# 1_P1.net
KiCad netlist of a schematic drawn in Altium Designer
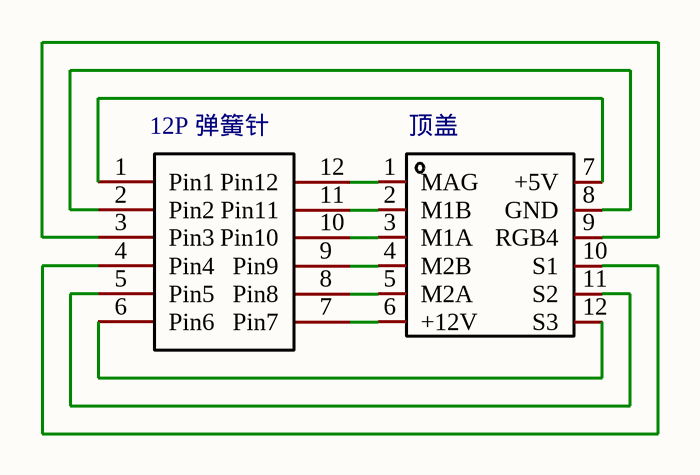
[diagram p0: 1_P1.schdoc]

(export (version "E")
  (design (tool "Eeschema 10.0.6"))
  (components
    (comp (ref "CN1")
      (value "顶盖")
      (description "系列:PHD;连接器类型:接头;触头类型:公形引脚;间距:0.079")
      (fields
        (field (name "DEVICE") "顶盖")
        (field (name "MANUFACTURER") "BOOMELE(博穆精密)")
        (field (name "MANUFACTURER PART") "PHD-2*6A")
      )
      (libsource (lib "altium-import") (part "root_0_顶盖_"))
    )
    (comp (ref "U1")
      (value "12P 弹簧针")
      (fields (field (name "DEVICE") "12P 弹簧针"))
      (libsource (lib "altium-import") (part "root_0_12P 弹簧针_"))
    )
  )
  (nets
    (net (code "1") (name "Net-(CN1-+5V)") (class "Default")
      (node (ref "CN1") (pin "7") (pinfunction "+5V_7") (pintype "passive"))
      (node (ref "U1") (pin "1") (pinfunction "Pin1_1") (pintype "passive"))
    )
    (net (code "2") (name "Net-(CN1-+12V)") (class "Default")
      (node (ref "CN1") (pin "6") (pinfunction "+12V_6") (pintype "passive"))
      (node (ref "U1") (pin "7") (pinfunction "Pin7_7") (pintype "passive"))
    )
    (net (code "3") (name "Net-(CN1-GND)") (class "Default")
      (node (ref "CN1") (pin "8") (pinfunction "GND_8") (pintype "passive"))
      (node (ref "U1") (pin "2") (pinfunction "Pin2_2") (pintype "passive"))
    )
    (net (code "4") (name "Net-(CN1-M1A)") (class "Default")
      (node (ref "CN1") (pin "3") (pinfunction "M1A_3") (pintype "passive"))
      (node (ref "U1") (pin "10") (pinfunction "Pin10_10") (pintype "passive"))
    )
    (net (code "5") (name "Net-(CN1-M1B)") (class "Default")
      (node (ref "CN1") (pin "2") (pinfunction "M1B_2") (pintype "passive"))
      (node (ref "U1") (pin "11") (pinfunction "Pin11_11") (pintype "passive"))
    )
    (net (code "6") (name "Net-(CN1-M2A)") (class "Default")
      (node (ref "CN1") (pin "5") (pinfunction "M2A_5") (pintype "passive"))
      (node (ref "U1") (pin "8") (pinfunction "Pin8_8") (pintype "passive"))
    )
    (net (code "7") (name "Net-(CN1-M2B)") (class "Default")
      (node (ref "CN1") (pin "4") (pinfunction "M2B_4") (pintype "passive"))
      (node (ref "U1") (pin "9") (pinfunction "Pin9_9") (pintype "passive"))
    )
    (net (code "8") (name "Net-(CN1-MAG)") (class "Default")
      (node (ref "CN1") (pin "1") (pinfunction "MAG_1") (pintype "passive"))
      (node (ref "U1") (pin "12") (pinfunction "Pin12_12") (pintype "passive"))
    )
    (net (code "9") (name "Net-(CN1-RGB4)") (class "Default")
      (node (ref "CN1") (pin "9") (pinfunction "RGB4_9") (pintype "passive"))
      (node (ref "U1") (pin "3") (pinfunction "Pin3_3") (pintype "passive"))
    )
    (net (code "10") (name "Net-(CN1-S1)") (class "Default")
      (node (ref "CN1") (pin "10") (pinfunction "S1_10") (pintype "passive"))
      (node (ref "U1") (pin "4") (pinfunction "Pin4_4") (pintype "passive"))
    )
    (net (code "11") (name "Net-(CN1-S2)") (class "Default")
      (node (ref "CN1") (pin "11") (pinfunction "S2_11") (pintype "passive"))
      (node (ref "U1") (pin "5") (pinfunction "Pin5_5") (pintype "passive"))
    )
    (net (code "12") (name "Net-(CN1-S3)") (class "Default")
      (node (ref "CN1") (pin "12") (pinfunction "S3_12") (pintype "passive"))
      (node (ref "U1") (pin "6") (pinfunction "Pin6_6") (pintype "passive"))
    )
  )
)
